# Power_MPU.net
KiCad netlist of a schematic drawn in Altium Designer
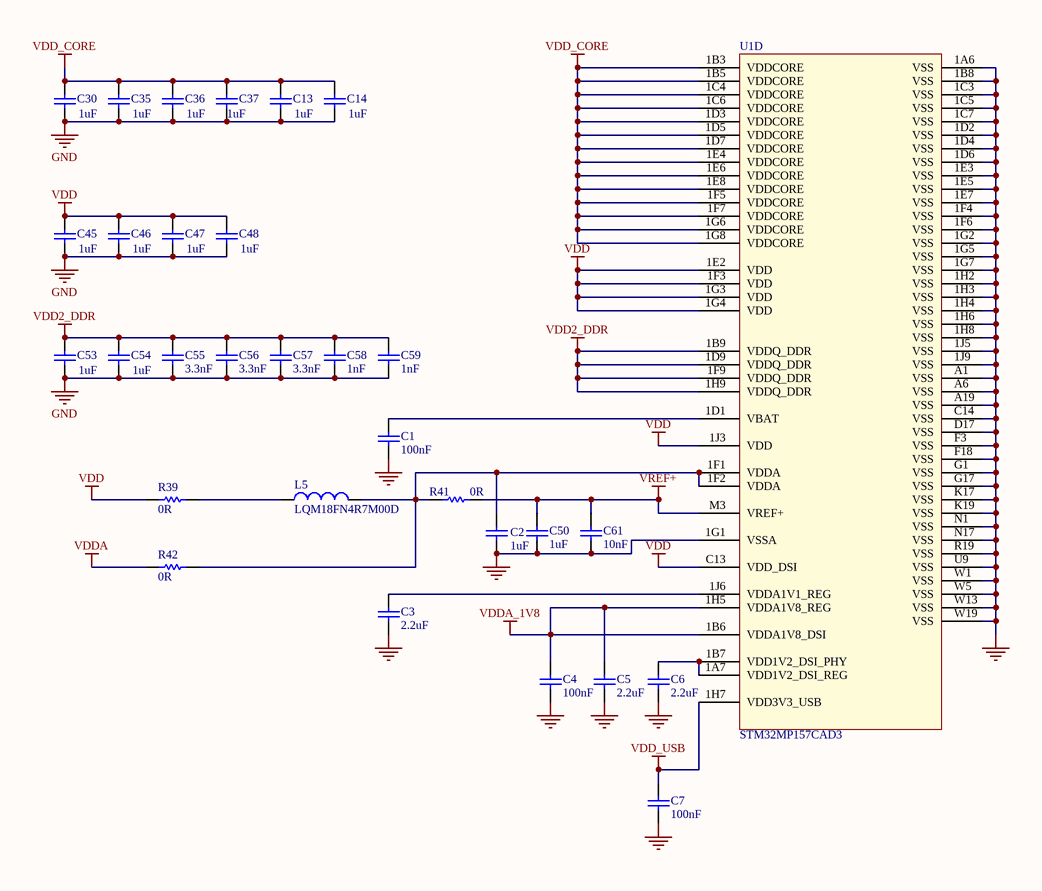
[diagram p0: Power_MPU.SchDoc]

(export (version "E")
  (design (tool "Eeschema 10.0.6"))
  (components
    (comp (ref "C1")
      (value "100nF")
      (footprint "C0402")
      (description "Capacitor, MLCC, 100nF, 16V, X7R, 10%, 0402, T=0.5mm")
      (fields
        (field (name "INTERNAL_PART_NUMBER") "MCD-00006")
        (field (name "MANUFACTURER_PART_NUMBER") "CC0402KRX7R7BB104")
        (field (name "PROVIDED_BY") "SUBCO")
      )
      (libsource (lib "MCD_PARTS_database") (part "Capacitor"))
    )
    (comp (ref "C2")
      (value "1uF")
      (footprint "C0402")
      (description "Capacitor, MLCC, 1uF, 25V, X5R, 10%, 0402, T=0,5mm")
      (fields
        (field (name "INTERNAL_PART_NUMBER") "MCD-00095")
        (field (name "MANUFACTURER_PART_NUMBER") "GRM155R61E105KA12")
        (field (name "PROVIDED_BY") "SUBCO")
      )
      (libsource (lib "MCD_PARTS_database") (part "Capacitor"))
    )
    (comp (ref "C3")
      (value "2.2uF")
      (footprint "C0402")
      (description "Capacitor,MLCC,2.2uF,6V3,X5R,10%,0402,T=0.5")
      (fields
        (field (name "INTERNAL_PART_NUMBER") "MCD-01823")
        (field (name "MANUFACTURER_PART_NUMBER") "GRM155R60J225KE95D")
        (field (name "PROVIDED_BY") "SUBCO")
      )
      (libsource (lib "MCD_PARTS_database") (part "Capacitor"))
    )
    (comp (ref "C4")
      (value "100nF")
      (footprint "C0402")
      (description "Capacitor, MLCC, 100nF, 16V, X7R, 10%, 0402, T=0.5mm")
      (fields
        (field (name "INTERNAL_PART_NUMBER") "MCD-00006")
        (field (name "MANUFACTURER_PART_NUMBER") "CC0402KRX7R7BB104")
        (field (name "PROVIDED_BY") "SUBCO")
      )
      (libsource (lib "MCD_PARTS_database") (part "Capacitor"))
    )
    (comp (ref "C5")
      (value "2.2uF")
      (footprint "C0402")
      (description "Capacitor,MLCC,2.2uF,6V3,X5R,10%,0402,T=0.5")
      (fields
        (field (name "INTERNAL_PART_NUMBER") "MCD-01823")
        (field (name "MANUFACTURER_PART_NUMBER") "GRM155R60J225KE95D")
        (field (name "PROVIDED_BY") "SUBCO")
      )
      (libsource (lib "MCD_PARTS_database") (part "Capacitor"))
    )
    (comp (ref "C6")
      (value "2.2uF")
      (footprint "C0402")
      (description "Capacitor,MLCC,2.2uF,6V3,X5R,10%,0402,T=0.5")
      (fields
        (field (name "INTERNAL_PART_NUMBER") "MCD-01823")
        (field (name "MANUFACTURER_PART_NUMBER") "GRM155R60J225KE95D")
        (field (name "PROVIDED_BY") "SUBCO")
      )
      (libsource (lib "MCD_PARTS_database") (part "Capacitor"))
    )
    (comp (ref "C7")
      (value "100nF")
      (footprint "C0402")
      (description "Capacitor, MLCC, 100nF, 16V, X7R, 10%, 0402, T=0.5mm")
      (fields
        (field (name "INTERNAL_PART_NUMBER") "MCD-00006")
        (field (name "MANUFACTURER_PART_NUMBER") "CC0402KRX7R7BB104")
        (field (name "PROVIDED_BY") "SUBCO")
      )
      (libsource (lib "MCD_PARTS_database") (part "Capacitor"))
    )
    (comp (ref "C13")
      (value "1uF")
      (footprint "C0402")
      (description "Capacitor, MLCC, 1uF, 25V, X5R, 10%, 0402, T=0,5mm")
      (fields
        (field (name "INTERNAL_PART_NUMBER") "MCD-00095")
        (field (name "MANUFACTURER_PART_NUMBER") "GRM155R61E105KA12")
        (field (name "PROVIDED_BY") "SUBCO")
      )
      (libsource (lib "MCD_PARTS_database") (part "Capacitor"))
    )
    (comp (ref "C14")
      (value "1uF")
      (footprint "C0402")
      (description "Capacitor, MLCC, 1uF, 25V, X5R, 10%, 0402, T=0,5mm")
      (fields
        (field (name "INTERNAL_PART_NUMBER") "MCD-00095")
        (field (name "MANUFACTURER_PART_NUMBER") "GRM155R61E105KA12")
        (field (name "PROVIDED_BY") "SUBCO")
      )
      (libsource (lib "MCD_PARTS_database") (part "Capacitor"))
    )
    (comp (ref "C30")
      (value "1uF")
      (footprint "C0402")
      (description "Capacitor, MLCC, 1uF, 25V, X5R, 10%, 0402, T=0,5mm")
      (fields
        (field (name "INTERNAL_PART_NUMBER") "MCD-00095")
        (field (name "MANUFACTURER_PART_NUMBER") "GRM155R61E105KA12")
        (field (name "PROVIDED_BY") "SUBCO")
      )
      (libsource (lib "MCD_PARTS_database") (part "Capacitor"))
    )
    (comp (ref "C35")
      (value "1uF")
      (footprint "C0402")
      (description "Capacitor, MLCC, 1uF, 25V, X5R, 10%, 0402, T=0,5mm")
      (fields
        (field (name "INTERNAL_PART_NUMBER") "MCD-00095")
        (field (name "MANUFACTURER_PART_NUMBER") "GRM155R61E105KA12")
        (field (name "PROVIDED_BY") "SUBCO")
      )
      (libsource (lib "MCD_PARTS_database") (part "Capacitor"))
    )
    (comp (ref "C36")
      (value "1uF")
      (footprint "C0402")
      (description "Capacitor, MLCC, 1uF, 25V, X5R, 10%, 0402, T=0,5mm")
      (fields
        (field (name "INTERNAL_PART_NUMBER") "MCD-00095")
        (field (name "MANUFACTURER_PART_NUMBER") "GRM155R61E105KA12")
        (field (name "PROVIDED_BY") "SUBCO")
      )
      (libsource (lib "MCD_PARTS_database") (part "Capacitor"))
    )
    (comp (ref "C37")
      (value "1uF")
      (footprint "C0402")
      (description "Capacitor, MLCC, 1uF, 25V, X5R, 10%, 0402, T=0,5mm")
      (fields
        (field (name "INTERNAL_PART_NUMBER") "MCD-00095")
        (field (name "MANUFACTURER_PART_NUMBER") "GRM155R61E105KA12")
        (field (name "PROVIDED_BY") "SUBCO")
      )
      (libsource (lib "MCD_PARTS_database") (part "Capacitor"))
    )
    (comp (ref "C45")
      (value "1uF")
      (footprint "C0402")
      (description "Capacitor, MLCC, 1uF, 25V, X5R, 10%, 0402, T=0,5mm")
      (fields
        (field (name "INTERNAL_PART_NUMBER") "MCD-00095")
        (field (name "MANUFACTURER_PART_NUMBER") "GRM155R61E105KA12")
        (field (name "PROVIDED_BY") "SUBCO")
      )
      (libsource (lib "MCD_PARTS_database") (part "Capacitor"))
    )
    (comp (ref "C46")
      (value "1uF")
      (footprint "C0402")
      (description "Capacitor, MLCC, 1uF, 25V, X5R, 10%, 0402, T=0,5mm")
      (fields
        (field (name "INTERNAL_PART_NUMBER") "MCD-00095")
        (field (name "MANUFACTURER_PART_NUMBER") "GRM155R61E105KA12")
        (field (name "PROVIDED_BY") "SUBCO")
      )
      (libsource (lib "MCD_PARTS_database") (part "Capacitor"))
    )
    (comp (ref "C47")
      (value "1uF")
      (footprint "C0402")
      (description "Capacitor, MLCC, 1uF, 25V, X5R, 10%, 0402, T=0,5mm")
      (fields
        (field (name "INTERNAL_PART_NUMBER") "MCD-00095")
        (field (name "MANUFACTURER_PART_NUMBER") "GRM155R61E105KA12")
        (field (name "PROVIDED_BY") "SUBCO")
      )
      (libsource (lib "MCD_PARTS_database") (part "Capacitor"))
    )
    (comp (ref "C48")
      (value "1uF")
      (footprint "C0402")
      (description "Capacitor, MLCC, 1uF, 25V, X5R, 10%, 0402, T=0,5mm")
      (fields
        (field (name "INTERNAL_PART_NUMBER") "MCD-00095")
        (field (name "MANUFACTURER_PART_NUMBER") "GRM155R61E105KA12")
        (field (name "PROVIDED_BY") "SUBCO")
      )
      (libsource (lib "MCD_PARTS_database") (part "Capacitor"))
    )
    (comp (ref "C50")
      (value "1uF")
      (footprint "C0402")
      (description "Capacitor, MLCC, 1uF, 25V, X5R, 10%, 0402, T=0,5mm")
      (fields
        (field (name "INTERNAL_PART_NUMBER") "MCD-00095")
        (field (name "MANUFACTURER_PART_NUMBER") "GRM155R61E105KA12")
        (field (name "PROVIDED_BY") "SUBCO")
      )
      (libsource (lib "MCD_PARTS_database") (part "Capacitor"))
    )
    (comp (ref "C53")
      (value "1uF")
      (footprint "C0402")
      (description "Capacitor, MLCC, 1uF, 25V, X5R, 10%, 0402, T=0,5mm")
      (fields
        (field (name "INTERNAL_PART_NUMBER") "MCD-00095")
        (field (name "MANUFACTURER_PART_NUMBER") "GRM155R61E105KA12")
        (field (name "PROVIDED_BY") "SUBCO")
      )
      (libsource (lib "MCD_PARTS_database") (part "Capacitor"))
    )
    (comp (ref "C54")
      (value "1uF")
      (footprint "C0402")
      (description "Capacitor, MLCC, 1uF, 25V, X5R, 10%, 0402, T=0,5mm")
      (fields
        (field (name "INTERNAL_PART_NUMBER") "MCD-00095")
        (field (name "MANUFACTURER_PART_NUMBER") "GRM155R61E105KA12")
        (field (name "PROVIDED_BY") "SUBCO")
      )
      (libsource (lib "MCD_PARTS_database") (part "Capacitor"))
    )
    (comp (ref "C55")
      (value "3.3nF")
      (footprint "C0402")
      (description "Capacitor, MLCC, 3.3nF, 16V, X7R, 10%, 0402, T=0.5mm")
      (fields
        (field (name "INTERNAL_PART_NUMBER") "MCD-01462")
        (field (name "MANUFACTURER_PART_NUMBER") "CC0402KRX7R7BB332")
        (field (name "PROVIDED_BY") "SUBCO")
      )
      (libsource (lib "MCD_PARTS_database") (part "Capacitor"))
    )
    (comp (ref "C56")
      (value "3.3nF")
      (footprint "C0402")
      (description "Capacitor, MLCC, 3.3nF, 16V, X7R, 10%, 0402, T=0.5mm")
      (fields
        (field (name "INTERNAL_PART_NUMBER") "MCD-01462")
        (field (name "MANUFACTURER_PART_NUMBER") "CC0402KRX7R7BB332")
        (field (name "PROVIDED_BY") "SUBCO")
      )
      (libsource (lib "MCD_PARTS_database") (part "Capacitor"))
    )
    (comp (ref "C57")
      (value "3.3nF")
      (footprint "C0402")
      (description "Capacitor, MLCC, 3.3nF, 16V, X7R, 10%, 0402, T=0.5mm")
      (fields
        (field (name "INTERNAL_PART_NUMBER") "MCD-01462")
        (field (name "MANUFACTURER_PART_NUMBER") "CC0402KRX7R7BB332")
        (field (name "PROVIDED_BY") "SUBCO")
      )
      (libsource (lib "MCD_PARTS_database") (part "Capacitor"))
    )
    (comp (ref "C58")
      (value "1nF")
      (footprint "C0402")
      (description "Capacitor, MLCC, 1nF, 16V, X7R, 10%, 0402, T=0.5mm")
      (fields
        (field (name "INTERNAL_PART_NUMBER") "MCD-00198")
        (field (name "MANUFACTURER_PART_NUMBER") "CC0402KRX7R7BB102")
        (field (name "PROVIDED_BY") "SUBCO")
      )
      (libsource (lib "MCD_PARTS_database") (part "Capacitor"))
    )
    (comp (ref "C59")
      (value "1nF")
      (footprint "C0402")
      (description "Capacitor, MLCC, 1nF, 16V, X7R, 10%, 0402, T=0.5mm")
      (fields
        (field (name "INTERNAL_PART_NUMBER") "MCD-00198")
        (field (name "MANUFACTURER_PART_NUMBER") "CC0402KRX7R7BB102")
        (field (name "PROVIDED_BY") "SUBCO")
      )
      (libsource (lib "MCD_PARTS_database") (part "Capacitor"))
    )
    (comp (ref "C61")
      (value "10nF")
      (footprint "C0402")
      (description "Capacitor, MLCC, 10nF, 16V, X7R, 10%, 0402, T=0.5mm")
      (fields
        (field (name "INTERNAL_PART_NUMBER") "MCD-00011")
        (field (name "MANUFACTURER_PART_NUMBER") "CC0402KRX7R7BB103")
        (field (name "PROVIDED_BY") "SUBCO")
      )
      (libsource (lib "MCD_PARTS_database") (part "Capacitor"))
    )
    (comp (ref "L5")
      (value "LQM18FN4R7M00D")
      (footprint "L0603_H0P8")
      (description "IND 4.7uH 20% 80mA 600mhom 0603")
      (fields
        (field (name "INTERNAL_PART_NUMBER") "MCD-01134")
        (field (name "MANUFACTURER") "MURATA")
        (field (name "PROVIDED_BY") "SUBCO")
      )
      (libsource (lib "MCD_PARTS_database") (part "LQM18FN4R7M00D"))
    )
    (comp (ref "R39")
      (value "0R")
      (footprint "R0402")
      (description "Resistor,0R,0402,5%,1/16W")
      (fields
        (field (name "INTERNAL_PART_NUMBER") "MCD-00052")
        (field (name "MANUFACTURER_PART_NUMBER") "RC0402JR-070RL")
        (field (name "PROVIDED_BY") "SUBCO")
      )
      (libsource (lib "MCD_PARTS_database") (part "Resistor"))
    )
    (comp (ref "R41")
      (value "0R")
      (footprint "R0402")
      (description "Resistor,0R,0402,5%,1/16W")
      (fields
        (field (name "INTERNAL_PART_NUMBER") "MCD-00052")
        (field (name "MANUFACTURER_PART_NUMBER") "RC0402JR-070RL")
        (field (name "PROVIDED_BY") "SUBCO")
      )
      (libsource (lib "MCD_PARTS_database") (part "Resistor"))
    )
    (comp (ref "R42")
      (value "0R")
      (footprint "R0402")
      (description "Resistor,0R,0402,5%,1/16W")
      (fields
        (field (name "INTERNAL_PART_NUMBER") "MCD-00052")
        (field (name "MANUFACTURER_PART_NUMBER") "RC0402JR-070RL")
        (field (name "PROVIDED_BY") "SUBCO")
      )
      (libsource (lib "MCD_PARTS_database") (part "Resistor"))
    )
    (comp (ref "U1")
      (value "STM32MP157CAD3")
      (footprint "ICC_TFBGA257_10X10_STM32MP157CAD3_P050-065")
      (description "MPU TFBGA10x10 secure boot+crypto")
      (fields
        (field (name "INTERNAL_PART_NUMBER") "MCD-01144")
        (field (name "MANUFACTURER") "STMICROELECTRONICS")
        (field (name "PROVIDED_BY") "SUBCO with ST control")
      )
      (libsource (lib "MCD_PARTS_database") (part "STM32MP157CAD3"))
    )
  )
  (nets
    (net (code "1") (name "GND") (class "Default")
      (node (ref "C1") (pin "1") (pinfunction "1_1") (pintype "passive"))
      (node (ref "C13") (pin "1") (pinfunction "1_1") (pintype "passive"))
      (node (ref "C14") (pin "1") (pinfunction "1_1") (pintype "passive"))
      (node (ref "C2") (pin "1") (pinfunction "1_1") (pintype "passive"))
      (node (ref "C3") (pin "1") (pinfunction "1_1") (pintype "passive"))
      (node (ref "C30") (pin "1") (pinfunction "1_1") (pintype "passive"))
      (node (ref "C35") (pin "1") (pinfunction "1_1") (pintype "passive"))
      (node (ref "C36") (pin "1") (pinfunction "1_1") (pintype "passive"))
      (node (ref "C37") (pin "1") (pinfunction "1_1") (pintype "passive"))
      (node (ref "C4") (pin "1") (pinfunction "1_1") (pintype "passive"))
      (node (ref "C45") (pin "1") (pinfunction "1_1") (pintype "passive"))
      (node (ref "C46") (pin "1") (pinfunction "1_1") (pintype "passive"))
      (node (ref "C47") (pin "1") (pinfunction "1_1") (pintype "passive"))
      (node (ref "C48") (pin "1") (pinfunction "1_1") (pintype "passive"))
      (node (ref "C5") (pin "1") (pinfunction "1_1") (pintype "passive"))
      (node (ref "C50") (pin "1") (pinfunction "1_1") (pintype "passive"))
      (node (ref "C53") (pin "1") (pinfunction "1_1") (pintype "passive"))
      (node (ref "C54") (pin "1") (pinfunction "1_1") (pintype "passive"))
      (node (ref "C55") (pin "1") (pinfunction "1_1") (pintype "passive"))
      (node (ref "C56") (pin "1") (pinfunction "1_1") (pintype "passive"))
      (node (ref "C57") (pin "1") (pinfunction "1_1") (pintype "passive"))
      (node (ref "C58") (pin "1") (pinfunction "1_1") (pintype "passive"))
      (node (ref "C59") (pin "1") (pinfunction "1_1") (pintype "passive"))
      (node (ref "C6") (pin "1") (pinfunction "1_1") (pintype "passive"))
      (node (ref "C61") (pin "1") (pinfunction "1_1") (pintype "passive"))
      (node (ref "C7") (pin "1") (pinfunction "1_1") (pintype "passive"))
      (node (ref "U1") (pin "1A6") (pinfunction "VSS_1A6") (pintype "passive"))
      (node (ref "U1") (pin "1B8") (pinfunction "VSS_1B8") (pintype "passive"))
      (node (ref "U1") (pin "1C3") (pinfunction "VSS_1C3") (pintype "passive"))
      (node (ref "U1") (pin "1C5") (pinfunction "VSS_1C5") (pintype "passive"))
      (node (ref "U1") (pin "1C7") (pinfunction "VSS_1C7") (pintype "passive"))
      (node (ref "U1") (pin "1D2") (pinfunction "VSS_1D2") (pintype "passive"))
      (node (ref "U1") (pin "1D4") (pinfunction "VSS_1D4") (pintype "passive"))
      (node (ref "U1") (pin "1D6") (pinfunction "VSS_1D6") (pintype "passive"))
      (node (ref "U1") (pin "1E3") (pinfunction "VSS_1E3") (pintype "passive"))
      (node (ref "U1") (pin "1E5") (pinfunction "VSS_1E5") (pintype "passive"))
      (node (ref "U1") (pin "1E7") (pinfunction "VSS_1E7") (pintype "passive"))
      (node (ref "U1") (pin "1F4") (pinfunction "VSS_1F4") (pintype "passive"))
      (node (ref "U1") (pin "1F6") (pinfunction "VSS_1F6") (pintype "passive"))
      (node (ref "U1") (pin "1G1") (pinfunction "VSSA_1G1") (pintype "passive"))
      (node (ref "U1") (pin "1G2") (pinfunction "VSS_1G2") (pintype "passive"))
      (node (ref "U1") (pin "1G5") (pinfunction "VSS_1G5") (pintype "passive"))
      (node (ref "U1") (pin "1G7") (pinfunction "VSS_1G7") (pintype "passive"))
      (node (ref "U1") (pin "1H2") (pinfunction "VSS_1H2") (pintype "passive"))
      (node (ref "U1") (pin "1H3") (pinfunction "VSS_1H3") (pintype "passive"))
      (node (ref "U1") (pin "1H4") (pinfunction "VSS_1H4") (pintype "passive"))
      (node (ref "U1") (pin "1H6") (pinfunction "VSS_1H6") (pintype "passive"))
      (node (ref "U1") (pin "1H8") (pinfunction "VSS_1H8") (pintype "passive"))
      (node (ref "U1") (pin "1J5") (pinfunction "VSS_1J5") (pintype "passive"))
      (node (ref "U1") (pin "1J9") (pinfunction "VSS_1J9") (pintype "passive"))
      (node (ref "U1") (pin "A1") (pinfunction "VSS_A1") (pintype "passive"))
      (node (ref "U1") (pin "A19") (pinfunction "VSS_A19") (pintype "passive"))
      (node (ref "U1") (pin "A6") (pinfunction "VSS_A6") (pintype "passive"))
      (node (ref "U1") (pin "C14") (pinfunction "VSS_C14") (pintype "passive"))
      (node (ref "U1") (pin "D17") (pinfunction "VSS_D17") (pintype "passive"))
      (node (ref "U1") (pin "F18") (pinfunction "VSS_F18") (pintype "passive"))
      (node (ref "U1") (pin "F3") (pinfunction "VSS_F3") (pintype "passive"))
      (node (ref "U1") (pin "G1") (pinfunction "VSS_G1") (pintype "passive"))
      (node (ref "U1") (pin "G17") (pinfunction "VSS_G17") (pintype "passive"))
      (node (ref "U1") (pin "K17") (pinfunction "VSS_K17") (pintype "passive"))
      (node (ref "U1") (pin "K19") (pinfunction "VSS_K19") (pintype "passive"))
      (node (ref "U1") (pin "N1") (pinfunction "VSS_N1") (pintype "passive"))
      (node (ref "U1") (pin "N17") (pinfunction "VSS_N17") (pintype "passive"))
      (node (ref "U1") (pin "R19") (pinfunction "VSS_R19") (pintype "passive"))
      (node (ref "U1") (pin "U9") (pinfunction "VSS_U9") (pintype "passive"))
      (node (ref "U1") (pin "W1") (pinfunction "VSS_W1") (pintype "passive"))
      (node (ref "U1") (pin "W13") (pinfunction "VSS_W13") (pintype "passive"))
      (node (ref "U1") (pin "W19") (pinfunction "VSS_W19") (pintype "passive"))
      (node (ref "U1") (pin "W5") (pinfunction "VSS_W5") (pintype "passive"))
    )
    (net (code "2") (name "Net-(C2-Pad2)") (class "Default")
      (node (ref "C2") (pin "2") (pinfunction "2_2") (pintype "passive"))
      (node (ref "L5") (pin "2") (pinfunction "2_2") (pintype "passive"))
      (node (ref "R41") (pin "1") (pinfunction "1_1") (pintype "passive"))
      (node (ref "R42") (pin "2") (pinfunction "2_2") (pintype "passive"))
      (node (ref "U1") (pin "1F1") (pinfunction "VDDA_1F1") (pintype "passive"))
      (node (ref "U1") (pin "1F2") (pinfunction "VDDA_1F2") (pintype "passive"))
    )
    (net (code "3") (name "Net-(L5-Pad1)") (class "Default")
      (node (ref "L5") (pin "1") (pinfunction "1_1") (pintype "passive"))
      (node (ref "R39") (pin "2") (pinfunction "2_2") (pintype "passive"))
    )
    (net (code "4") (name "Net-(U1D-VBAT)") (class "Default")
      (node (ref "C1") (pin "2") (pinfunction "2_2") (pintype "passive"))
      (node (ref "U1") (pin "1D1") (pinfunction "VBAT_1D1") (pintype "passive"))
    )
    (net (code "5") (name "Net-(U1D-VDD1V2_DSI_PHY)") (class "Default")
      (node (ref "C6") (pin "2") (pinfunction "2_2") (pintype "passive"))
      (node (ref "U1") (pin "1A7") (pinfunction "VDD1V2_DSI_REG_1A7") (pintype "passive"))
      (node (ref "U1") (pin "1B7") (pinfunction "VDD1V2_DSI_PHY_1B7") (pintype "passive"))
    )
    (net (code "6") (name "Net-(U1D-VDDA1V1_REG)") (class "Default")
      (node (ref "C3") (pin "2") (pinfunction "2_2") (pintype "passive"))
      (node (ref "U1") (pin "1J6") (pinfunction "VDDA1V1_REG_1J6") (pintype "passive"))
    )
    (net (code "7") (name "VDD") (class "Default")
      (node (ref "C45") (pin "2") (pinfunction "2_2") (pintype "passive"))
      (node (ref "C46") (pin "2") (pinfunction "2_2") (pintype "passive"))
      (node (ref "C47") (pin "2") (pinfunction "2_2") (pintype "passive"))
      (node (ref "C48") (pin "2") (pinfunction "2_2") (pintype "passive"))
      (node (ref "R39") (pin "1") (pinfunction "1_1") (pintype "passive"))
      (node (ref "U1") (pin "1E2") (pinfunction "VDD_1E2") (pintype "passive"))
      (node (ref "U1") (pin "1F3") (pinfunction "VDD_1F3") (pintype "passive"))
      (node (ref "U1") (pin "1G3") (pinfunction "VDD_1G3") (pintype "passive"))
      (node (ref "U1") (pin "1G4") (pinfunction "VDD_1G4") (pintype "passive"))
      (node (ref "U1") (pin "1J3") (pinfunction "VDD_1J3") (pintype "passive"))
      (node (ref "U1") (pin "C13") (pinfunction "VDD_DSI_C13") (pintype "passive"))
    )
    (net (code "8") (name "VDD2_DDR") (class "Default")
      (node (ref "C53") (pin "2") (pinfunction "2_2") (pintype "passive"))
      (node (ref "C54") (pin "2") (pinfunction "2_2") (pintype "passive"))
      (node (ref "C55") (pin "2") (pinfunction "2_2") (pintype "passive"))
      (node (ref "C56") (pin "2") (pinfunction "2_2") (pintype "passive"))
      (node (ref "C57") (pin "2") (pinfunction "2_2") (pintype "passive"))
      (node (ref "C58") (pin "2") (pinfunction "2_2") (pintype "passive"))
      (node (ref "C59") (pin "2") (pinfunction "2_2") (pintype "passive"))
      (node (ref "U1") (pin "1B9") (pinfunction "VDDQ_DDR_1B9") (pintype "passive"))
      (node (ref "U1") (pin "1D9") (pinfunction "VDDQ_DDR_1D9") (pintype "passive"))
      (node (ref "U1") (pin "1F9") (pinfunction "VDDQ_DDR_1F9") (pintype "passive"))
      (node (ref "U1") (pin "1H9") (pinfunction "VDDQ_DDR_1H9") (pintype "passive"))
    )
    (net (code "9") (name "VDDA") (class "Default")
      (node (ref "R42") (pin "1") (pinfunction "1_1") (pintype "passive"))
    )
    (net (code "10") (name "VDDA_1V8") (class "Default")
      (node (ref "C4") (pin "2") (pinfunction "2_2") (pintype "passive"))
      (node (ref "C5") (pin "2") (pinfunction "2_2") (pintype "passive"))
      (node (ref "U1") (pin "1B6") (pinfunction "VDDA1V8_DSI_1B6") (pintype "passive"))
      (node (ref "U1") (pin "1H5") (pinfunction "VDDA1V8_REG_1H5") (pintype "passive"))
    )
    (net (code "11") (name "VDD_CORE") (class "Default")
      (node (ref "C13") (pin "2") (pinfunction "2_2") (pintype "passive"))
      (node (ref "C14") (pin "2") (pinfunction "2_2") (pintype "passive"))
      (node (ref "C30") (pin "2") (pinfunction "2_2") (pintype "passive"))
      (node (ref "C35") (pin "2") (pinfunction "2_2") (pintype "passive"))
      (node (ref "C36") (pin "2") (pinfunction "2_2") (pintype "passive"))
      (node (ref "C37") (pin "2") (pinfunction "2_2") (pintype "passive"))
      (node (ref "U1") (pin "1B3") (pinfunction "VDDCORE_1B3") (pintype "passive"))
      (node (ref "U1") (pin "1B5") (pinfunction "VDDCORE_1B5") (pintype "passive"))
      (node (ref "U1") (pin "1C4") (pinfunction "VDDCORE_1C4") (pintype "passive"))
      (node (ref "U1") (pin "1C6") (pinfunction "VDDCORE_1C6") (pintype "passive"))
      (node (ref "U1") (pin "1D3") (pinfunction "VDDCORE_1D3") (pintype "passive"))
      (node (ref "U1") (pin "1D5") (pinfunction "VDDCORE_1D5") (pintype "passive"))
      (node (ref "U1") (pin "1D7") (pinfunction "VDDCORE_1D7") (pintype "passive"))
      (node (ref "U1") (pin "1E4") (pinfunction "VDDCORE_1E4") (pintype "passive"))
      (node (ref "U1") (pin "1E6") (pinfunction "VDDCORE_1E6") (pintype "passive"))
      (node (ref "U1") (pin "1E8") (pinfunction "VDDCORE_1E8") (pintype "passive"))
      (node (ref "U1") (pin "1F5") (pinfunction "VDDCORE_1F5") (pintype "passive"))
      (node (ref "U1") (pin "1F7") (pinfunction "VDDCORE_1F7") (pintype "passive"))
      (node (ref "U1") (pin "1G6") (pinfunction "VDDCORE_1G6") (pintype "passive"))
      (node (ref "U1") (pin "1G8") (pinfunction "VDDCORE_1G8") (pintype "passive"))
    )
    (net (code "12") (name "VDD_USB") (class "Default")
      (node (ref "C7") (pin "2") (pinfunction "2_2") (pintype "passive"))
      (node (ref "U1") (pin "1H7") (pinfunction "VDD3V3_USB_1H7") (pintype "passive"))
    )
    (net (code "13") (name "VREF+") (class "Default")
      (node (ref "C50") (pin "2") (pinfunction "2_2") (pintype "passive"))
      (node (ref "C61") (pin "2") (pinfunction "2_2") (pintype "passive"))
      (node (ref "R41") (pin "2") (pinfunction "2_2") (pintype "passive"))
      (node (ref "U1") (pin "M3") (pinfunction "VREF+_M3") (pintype "passive"))
    )
  )
)
